# ignition_board_sch.net
KiCad netlist of a schematic drawn in EAGLE
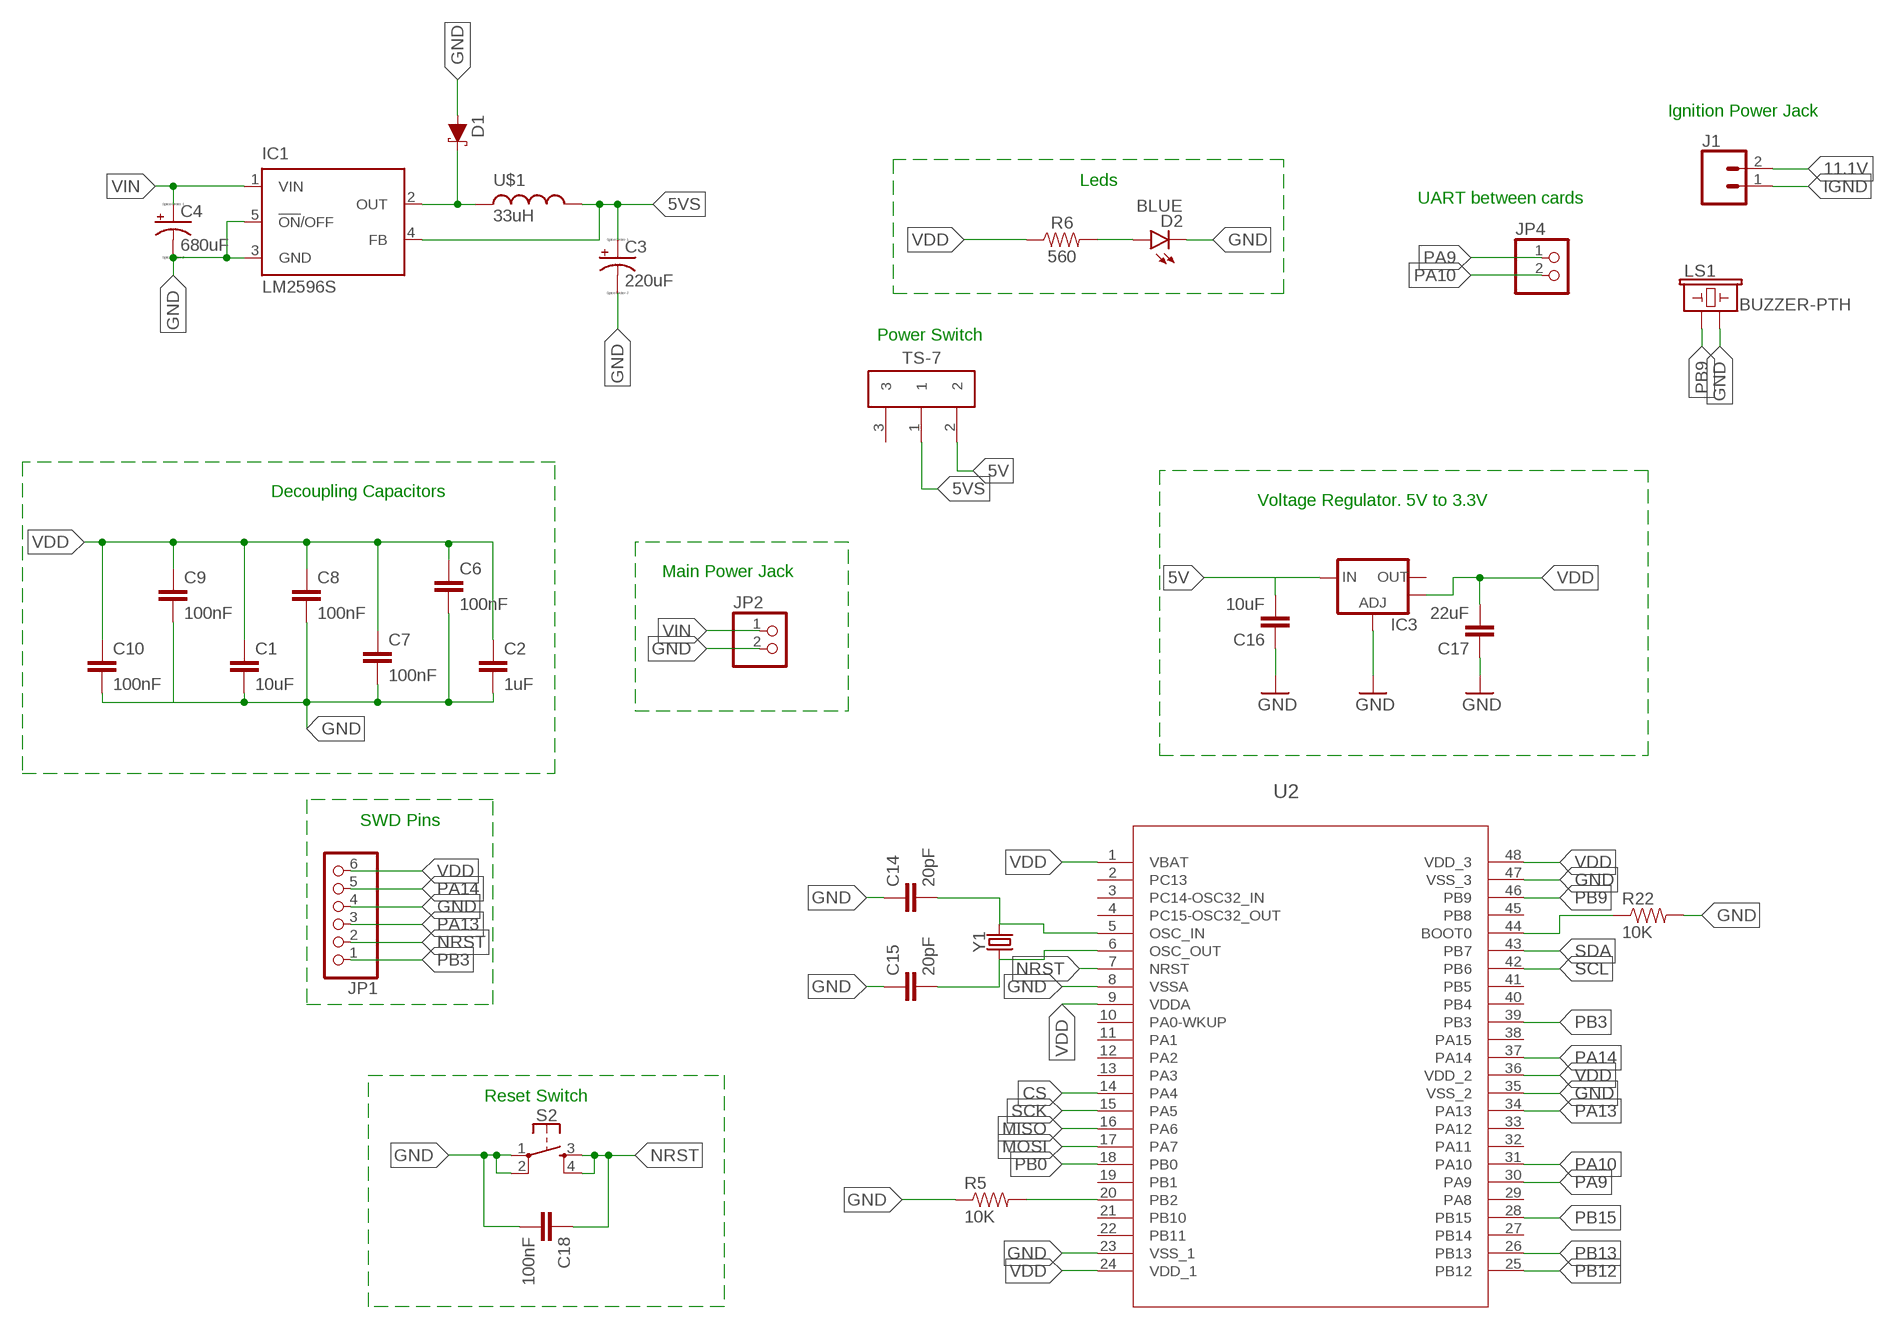
[diagram p0: schematic, sheet 1, part 1 of 2]
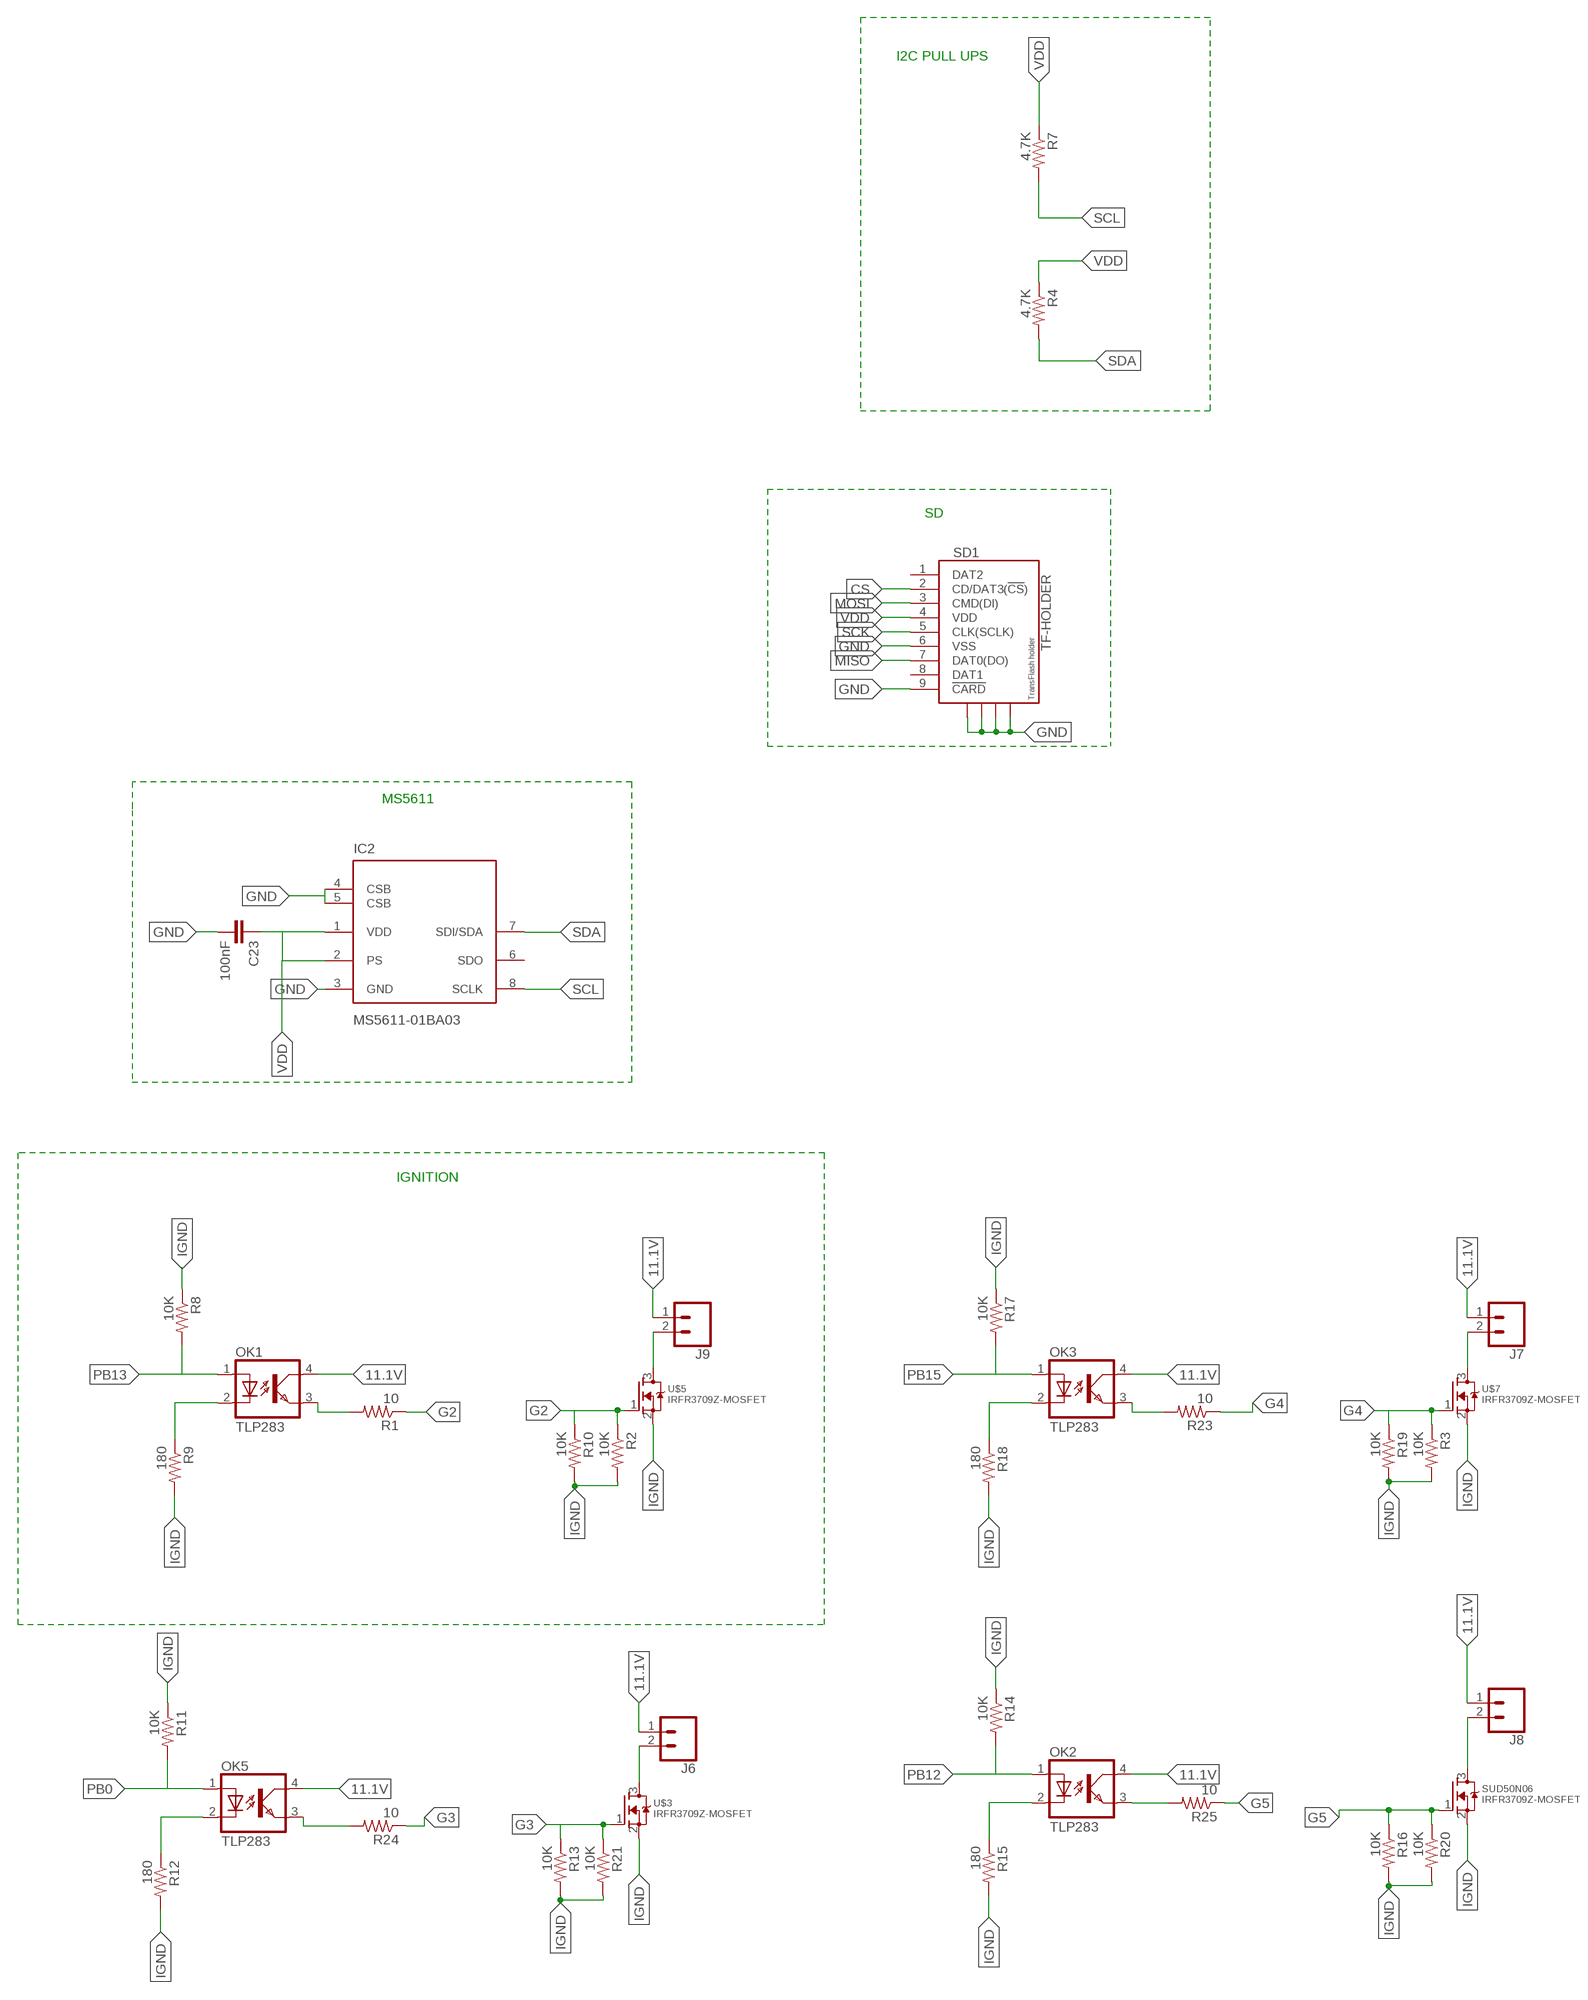
[diagram p1: schematic, sheet 1, part 2 of 2]

(export (version "E")
  (design (tool "Eeschema 10.0.6"))
  (components
    (comp (ref "C1")
      (value "10uF")
      (footprint "eagle-import:0805")
      (libsource (lib "eagle-import") (part "10UF-0805-10V-10%"))
    )
    (comp (ref "C2")
      (value "1uF")
      (footprint "eagle-import:0805")
      (libsource (lib "eagle-import") (part "10UF-0805-10V-10%"))
    )
    (comp (ref "C3")
      (value "220uF")
      (footprint "eagle-import:TT5D7")
      (libsource (lib "eagle-import") (part "CPOL-USTT5D7"))
    )
    (comp (ref "C4")
      (value "680uF")
      (footprint "eagle-import:TT5D7")
      (libsource (lib "eagle-import") (part "CPOL-USTT5D7"))
    )
    (comp (ref "C6")
      (value "100nF")
      (footprint "eagle-import:0805")
      (libsource (lib "eagle-import") (part "10UF-0805-10V-10%"))
    )
    (comp (ref "C7")
      (value "100nF")
      (footprint "eagle-import:0805")
      (libsource (lib "eagle-import") (part "10UF-0805-10V-10%"))
    )
    (comp (ref "C8")
      (value "100nF")
      (footprint "eagle-import:0805")
      (libsource (lib "eagle-import") (part "10UF-0805-10V-10%"))
    )
    (comp (ref "C9")
      (value "100nF")
      (footprint "eagle-import:0805")
      (libsource (lib "eagle-import") (part "10UF-0805-10V-10%"))
    )
    (comp (ref "C10")
      (value "100nF")
      (footprint "eagle-import:0805")
      (libsource (lib "eagle-import") (part "10UF-0805-10V-10%"))
    )
    (comp (ref "C14")
      (value "20pF")
      (footprint "eagle-import:0805")
      (libsource (lib "eagle-import") (part "10UF-0805-10V-10%"))
    )
    (comp (ref "C15")
      (value "20pF")
      (footprint "eagle-import:0805")
      (libsource (lib "eagle-import") (part "10UF-0805-10V-10%"))
    )
    (comp (ref "C16")
      (value "10uF")
      (footprint "eagle-import:0805@2")
      (libsource (lib "eagle-import") (part "CAP0805"))
    )
    (comp (ref "C17")
      (value "22uF")
      (footprint "eagle-import:0805@2")
      (libsource (lib "eagle-import") (part "CAP0805"))
    )
    (comp (ref "C18")
      (value "100nF")
      (footprint "eagle-import:0805")
      (libsource (lib "eagle-import") (part "10UF-0805-10V-10%"))
    )
    (comp (ref "C23")
      (value "100nF")
      (footprint "eagle-import:0805@2")
      (libsource (lib "eagle-import") (part "CAP0805"))
    )
    (comp (ref "D1")
      (value "3A/40V/500mV")
      (footprint "eagle-import:SMA-DIODE")
      (libsource (lib "eagle-import") (part "DIODE-SCHOTTKY-B340A"))
    )
    (comp (ref "D2")
      (value "BLUE")
      (footprint "eagle-import:LED-1206")
      (libsource (lib "eagle-import") (part "LED-BLUE1206"))
    )
    (comp (ref "IC1")
      (value "LM2596S")
      (footprint "eagle-import:TO263-5")
      (fields (field (name "MF") "NATIONAL SEMICONDUCTOR") (field (name "MPN") "LM2596S-ADJ/NOPB"))
      (libsource (lib "eagle-import") (part "LM2596S"))
    )
    (comp (ref "IC2")
      (value "MS5611-01BA03")
      (footprint "eagle-import:SON125P300X500X100-8N")
      (libsource (lib "eagle-import") (part "MS5611-01BA03"))
    )
    (comp (ref "IC3")
      (value "V_REG_LM1117SOT223")
      (footprint "eagle-import:SOT223")
      (libsource (lib "eagle-import") (part "V_REG_LM1117SOT223"))
    )
    (comp (ref "J1")
      (value "CONN_025MM")
      (footprint "eagle-import:SCREWTERMINAL-5MM-2")
      (libsource (lib "eagle-import") (part "CONN_025MM"))
    )
    (comp (ref "J6")
      (value "CONN_025MM")
      (footprint "eagle-import:SCREWTERMINAL-5MM-2")
      (libsource (lib "eagle-import") (part "CONN_025MM"))
    )
    (comp (ref "J7")
      (value "CONN_025MM")
      (footprint "eagle-import:SCREWTERMINAL-5MM-2")
      (libsource (lib "eagle-import") (part "CONN_025MM"))
    )
    (comp (ref "J8")
      (value "CONN_025MM")
      (footprint "eagle-import:SCREWTERMINAL-5MM-2")
      (libsource (lib "eagle-import") (part "CONN_025MM"))
    )
    (comp (ref "J9")
      (value "CONN_025MM")
      (footprint "eagle-import:SCREWTERMINAL-5MM-2")
      (libsource (lib "eagle-import") (part "CONN_025MM"))
    )
    (comp (ref "JP1")
      (value "PINHD-1X6")
      (footprint "eagle-import:1X06")
      (libsource (lib "eagle-import") (part "PINHD-1X6"))
    )
    (comp (ref "JP2")
      (value "PINHD-1X2")
      (footprint "eagle-import:1X02")
      (libsource (lib "eagle-import") (part "PINHD-1X2"))
    )
    (comp (ref "JP4")
      (value "PINHD-1X2/90")
      (footprint "eagle-import:1X02_90")
      (libsource (lib "eagle-import") (part "PINHD-1X2/90"))
    )
    (comp (ref "LS1")
      (value "BUZZER-PTH")
      (footprint "eagle-import:BUZZER-12MM")
      (libsource (lib "eagle-import") (part "BUZZER-PTH"))
    )
    (comp (ref "OK1")
      (value "TLP283")
      (footprint "eagle-import:MINI-FLAT-4")
      (libsource (lib "eagle-import") (part "TLP283"))
    )
    (comp (ref "OK2")
      (value "TLP283")
      (footprint "eagle-import:MINI-FLAT-4")
      (libsource (lib "eagle-import") (part "TLP283"))
    )
    (comp (ref "OK3")
      (value "TLP283")
      (footprint "eagle-import:MINI-FLAT-4")
      (libsource (lib "eagle-import") (part "TLP283"))
    )
    (comp (ref "OK5")
      (value "TLP283")
      (footprint "eagle-import:MINI-FLAT-4")
      (libsource (lib "eagle-import") (part "TLP283"))
    )
    (comp (ref "R1")
      (value "10")
      (footprint "eagle-import:0805")
      (libsource (lib "eagle-import") (part "RESISTOR0805-RES"))
    )
    (comp (ref "R2")
      (value "10K")
      (footprint "eagle-import:0805")
      (libsource (lib "eagle-import") (part "RESISTOR0805-RES"))
    )
    (comp (ref "R3")
      (value "10K")
      (footprint "eagle-import:0805")
      (libsource (lib "eagle-import") (part "RESISTOR0805-RES"))
    )
    (comp (ref "R4")
      (value "4.7K")
      (footprint "eagle-import:0805")
      (libsource (lib "eagle-import") (part "RESISTOR0805-RES"))
    )
    (comp (ref "R5")
      (value "10K")
      (footprint "eagle-import:0805")
      (libsource (lib "eagle-import") (part "RESISTOR0805-RES"))
    )
    (comp (ref "R6")
      (value "560")
      (footprint "eagle-import:0805@1")
      (libsource (lib "eagle-import") (part "0.3OHM-0805-1/8W-1%"))
    )
    (comp (ref "R7")
      (value "4.7K")
      (footprint "eagle-import:0805")
      (libsource (lib "eagle-import") (part "RESISTOR0805-RES"))
    )
    (comp (ref "R8")
      (value "10K")
      (footprint "eagle-import:0805")
      (libsource (lib "eagle-import") (part "RESISTOR0805-RES"))
    )
    (comp (ref "R9")
      (value "180")
      (footprint "eagle-import:0805")
      (libsource (lib "eagle-import") (part "RESISTOR0805-RES"))
    )
    (comp (ref "R10")
      (value "10K")
      (footprint "eagle-import:0805")
      (libsource (lib "eagle-import") (part "RESISTOR0805-RES"))
    )
    (comp (ref "R11")
      (value "10K")
      (footprint "eagle-import:0805")
      (libsource (lib "eagle-import") (part "RESISTOR0805-RES"))
    )
    (comp (ref "R12")
      (value "180")
      (footprint "eagle-import:0805")
      (libsource (lib "eagle-import") (part "RESISTOR0805-RES"))
    )
    (comp (ref "R13")
      (value "10K")
      (footprint "eagle-import:0805")
      (libsource (lib "eagle-import") (part "RESISTOR0805-RES"))
    )
    (comp (ref "R14")
      (value "10K")
      (footprint "eagle-import:0805")
      (libsource (lib "eagle-import") (part "RESISTOR0805-RES"))
    )
    (comp (ref "R15")
      (value "180")
      (footprint "eagle-import:0805")
      (libsource (lib "eagle-import") (part "RESISTOR0805-RES"))
    )
    (comp (ref "R16")
      (value "10K")
      (footprint "eagle-import:0805")
      (libsource (lib "eagle-import") (part "RESISTOR0805-RES"))
    )
    (comp (ref "R17")
      (value "10K")
      (footprint "eagle-import:0805")
      (libsource (lib "eagle-import") (part "RESISTOR0805-RES"))
    )
    (comp (ref "R18")
      (value "180")
      (footprint "eagle-import:0805")
      (libsource (lib "eagle-import") (part "RESISTOR0805-RES"))
    )
    (comp (ref "R19")
      (value "10K")
      (footprint "eagle-import:0805")
      (libsource (lib "eagle-import") (part "RESISTOR0805-RES"))
    )
    (comp (ref "R20")
      (value "10K")
      (footprint "eagle-import:0805")
      (libsource (lib "eagle-import") (part "RESISTOR0805-RES"))
    )
    (comp (ref "R21")
      (value "10K")
      (footprint "eagle-import:0805")
      (libsource (lib "eagle-import") (part "RESISTOR0805-RES"))
    )
    (comp (ref "R22")
      (value "10K")
      (footprint "eagle-import:0805")
      (libsource (lib "eagle-import") (part "RESISTOR0805-RES"))
    )
    (comp (ref "R23")
      (value "10")
      (footprint "eagle-import:0805")
      (libsource (lib "eagle-import") (part "RESISTOR0805-RES"))
    )
    (comp (ref "R24")
      (value "10")
      (footprint "eagle-import:0805")
      (libsource (lib "eagle-import") (part "RESISTOR0805-RES"))
    )
    (comp (ref "R25")
      (value "10")
      (footprint "eagle-import:0805")
      (libsource (lib "eagle-import") (part "RESISTOR0805-RES"))
    )
    (comp (ref "S2")
      (value "MOMENTARY-SWITCH-SPST-2-SMD-5.2MM")
      (footprint "eagle-import:TACTILE_SWITCH_SMD_5.2MM")
      (libsource (lib "eagle-import") (part "MOMENTARY-SWITCH-SPST-2-SMD-5.2MM"))
    )
    (comp (ref "SD1")
      (value "TF-HOLDER")
      (footprint "eagle-import:TF-PULL")
      (libsource (lib "eagle-import") (part "TF-HOLDER"))
    )
    (comp (ref "SUD50N06")
      (value "IRFR3709Z-MOSFET")
      (footprint "eagle-import:TO252")
      (libsource (lib "eagle-import") (part "IRFR3709Z-MOSFET"))
    )
    (comp (ref "TS-7")
      (value "TS-7")
      (footprint "eagle-import:TS7")
      (libsource (lib "eagle-import") (part "TS-7"))
    )
    (comp (ref "U$1")
      (value "33uH")
      (footprint "eagle-import:MSS1260")
      (libsource (lib "eagle-import") (part "MSS1260"))
    )
    (comp (ref "U$3")
      (value "IRFR3709Z-MOSFET")
      (footprint "eagle-import:TO252")
      (libsource (lib "eagle-import") (part "IRFR3709Z-MOSFET"))
    )
    (comp (ref "U$5")
      (value "IRFR3709Z-MOSFET")
      (footprint "eagle-import:TO252")
      (libsource (lib "eagle-import") (part "IRFR3709Z-MOSFET"))
    )
    (comp (ref "U$7")
      (value "IRFR3709Z-MOSFET")
      (footprint "eagle-import:TO252")
      (libsource (lib "eagle-import") (part "IRFR3709Z-MOSFET"))
    )
    (comp (ref "U2")
      (value "STM32F103CXT2")
      (footprint "eagle-import:LQFP48-7X7MM")
      (fields (field (name "MANUFACTURER_PART_NUMBER") "stm32f103cxt2"))
      (libsource (lib "eagle-import") (part "STM32F103CXT2"))
    )
    (comp (ref "Y1")
      (value "CRYSTALPTH-HC49US")
      (footprint "eagle-import:HC49US")
      (libsource (lib "eagle-import") (part "CRYSTALPTH-HC49US"))
    )
  )
  (nets
    (net (code "1") (name "5V") (class "Default")
      (node (ref "C16") (pin "2") (pinfunction "2_2") (pintype "passive"))
      (node (ref "IC3") (pin "3") (pinfunction "IN_3") (pintype "input"))
      (node (ref "TS-7") (pin "2") (pinfunction "2_2") (pintype "bidirectional"))
    )
    (net (code "2") (name "5VS") (class "Default")
      (node (ref "C3") (pin "+") (pinfunction "+_+") (pintype "passive"))
      (node (ref "IC1") (pin "4") (pinfunction "FB_4") (pintype "input"))
      (node (ref "TS-7") (pin "1") (pinfunction "1_1") (pintype "bidirectional"))
      (node (ref "U$1") (pin "P$1") (pinfunction "P$1_P$1") (pintype "passive"))
    )
    (net (code "3") (name "11.1V") (class "Default")
      (node (ref "J1") (pin "2") (pinfunction "2_2") (pintype "passive"))
      (node (ref "J6") (pin "1") (pinfunction "1_1") (pintype "passive"))
      (node (ref "J7") (pin "1") (pinfunction "1_1") (pintype "passive"))
      (node (ref "J8") (pin "1") (pinfunction "1_1") (pintype "passive"))
      (node (ref "J9") (pin "1") (pinfunction "1_1") (pintype "passive"))
      (node (ref "OK1") (pin "4") (pinfunction "COL_4") (pintype "passive"))
      (node (ref "OK2") (pin "4") (pinfunction "COL_4") (pintype "passive"))
      (node (ref "OK3") (pin "4") (pinfunction "COL_4") (pintype "passive"))
      (node (ref "OK5") (pin "4") (pinfunction "COL_4") (pintype "passive"))
    )
    (net (code "4") (name "CS") (class "Default")
      (node (ref "SD1") (pin "2") (pinfunction "CD/DAT3(~{CS})_2") (pintype "bidirectional"))
      (node (ref "U2") (pin "14") (pinfunction "PA4_14") (pintype "bidirectional"))
    )
    (net (code "5") (name "G2") (class "Default")
      (node (ref "R1") (pin "1") (pinfunction "1_1") (pintype "passive"))
      (node (ref "R10") (pin "1") (pinfunction "1_1") (pintype "passive"))
      (node (ref "R2") (pin "1") (pinfunction "1_1") (pintype "passive"))
      (node (ref "U$5") (pin "1") (pinfunction "G_1") (pintype "bidirectional"))
    )
    (net (code "6") (name "G3") (class "Default")
      (node (ref "R13") (pin "1") (pinfunction "1_1") (pintype "passive"))
      (node (ref "R21") (pin "1") (pinfunction "1_1") (pintype "passive"))
      (node (ref "R24") (pin "1") (pinfunction "1_1") (pintype "passive"))
      (node (ref "U$3") (pin "1") (pinfunction "G_1") (pintype "bidirectional"))
    )
    (net (code "7") (name "G4") (class "Default")
      (node (ref "R19") (pin "1") (pinfunction "1_1") (pintype "passive"))
      (node (ref "R23") (pin "1") (pinfunction "1_1") (pintype "passive"))
      (node (ref "R3") (pin "1") (pinfunction "1_1") (pintype "passive"))
      (node (ref "U$7") (pin "1") (pinfunction "G_1") (pintype "bidirectional"))
    )
    (net (code "8") (name "G5") (class "Default")
      (node (ref "R16") (pin "1") (pinfunction "1_1") (pintype "passive"))
      (node (ref "R20") (pin "1") (pinfunction "1_1") (pintype "passive"))
      (node (ref "R25") (pin "1") (pinfunction "1_1") (pintype "passive"))
      (node (ref "SUD50N06") (pin "1") (pinfunction "G_1") (pintype "bidirectional"))
    )
    (net (code "9") (name "GND") (class "Default")
      (node (ref "C1") (pin "2") (pinfunction "2_2") (pintype "passive"))
      (node (ref "C10") (pin "2") (pinfunction "2_2") (pintype "passive"))
      (node (ref "C14") (pin "1") (pinfunction "1_1") (pintype "passive"))
      (node (ref "C15") (pin "1") (pinfunction "1_1") (pintype "passive"))
      (node (ref "C16") (pin "1") (pinfunction "1_1") (pintype "passive"))
      (node (ref "C17") (pin "1") (pinfunction "1_1") (pintype "passive"))
      (node (ref "C18") (pin "2") (pinfunction "2_2") (pintype "passive"))
      (node (ref "C2") (pin "2") (pinfunction "2_2") (pintype "passive"))
      (node (ref "C23") (pin "2") (pinfunction "2_2") (pintype "passive"))
      (node (ref "C3") (pin "-") (pinfunction "-_-") (pintype "passive"))
      (node (ref "C4") (pin "-") (pinfunction "-_-") (pintype "passive"))
      (node (ref "C6") (pin "2") (pinfunction "2_2") (pintype "passive"))
      (node (ref "C7") (pin "2") (pinfunction "2_2") (pintype "passive"))
      (node (ref "C8") (pin "2") (pinfunction "2_2") (pintype "passive"))
      (node (ref "C9") (pin "2") (pinfunction "2_2") (pintype "passive"))
      (node (ref "D1") (pin "A") (pinfunction "A_A") (pintype "passive"))
      (node (ref "D2") (pin "C") (pinfunction "C_C") (pintype "passive"))
      (node (ref "IC1") (pin "3") (pinfunction "GND_3") (pintype "power_in"))
      (node (ref "IC1") (pin "5") (pinfunction "~{ON}/OFF_5") (pintype "input"))
      (node (ref "IC2") (pin "3") (pinfunction "GND_3") (pintype "power_in"))
      (node (ref "IC2") (pin "4") (pinfunction "CSB_4") (pintype "input"))
      (node (ref "IC2") (pin "5") (pinfunction "CSB_5") (pintype "input"))
      (node (ref "IC3") (pin "1") (pinfunction "ADJ_1") (pintype "input"))
      (node (ref "JP1") (pin "4") (pinfunction "4_4") (pintype "passive"))
      (node (ref "JP2") (pin "2") (pinfunction "2_2") (pintype "passive"))
      (node (ref "LS1") (pin "-") (pinfunction "2_-") (pintype "passive"))
      (node (ref "R22") (pin "2") (pinfunction "2_2") (pintype "passive"))
      (node (ref "R5") (pin "1") (pinfunction "1_1") (pintype "passive"))
      (node (ref "S2") (pin "1") (pinfunction "1_1") (pintype "passive"))
      (node (ref "S2") (pin "2") (pinfunction "2_2") (pintype "passive"))
      (node (ref "SD1") (pin "6") (pinfunction "VSS_6") (pintype "power_in"))
      (node (ref "SD1") (pin "9") (pinfunction "~{CARD}_9") (pintype "passive"))
      (node (ref "SD1") (pin "S1") (pinfunction "S1_S1") (pintype "passive"))
      (node (ref "SD1") (pin "S2") (pinfunction "S2_S2") (pintype "passive"))
      (node (ref "SD1") (pin "S3") (pinfunction "S3_S3") (pintype "passive"))
      (node (ref "SD1") (pin "S4") (pinfunction "S4_S4") (pintype "passive"))
      (node (ref "U2") (pin "23") (pinfunction "VSS_1_23") (pintype "power_in"))
      (node (ref "U2") (pin "35") (pinfunction "VSS_2_35") (pintype "power_in"))
      (node (ref "U2") (pin "47") (pinfunction "VSS_3_47") (pintype "power_in"))
      (node (ref "U2") (pin "8") (pinfunction "VSSA_8") (pintype "power_in"))
    )
    (net (code "10") (name "IGND") (class "Default")
      (node (ref "J1") (pin "1") (pinfunction "1_1") (pintype "passive"))
      (node (ref "R10") (pin "2") (pinfunction "2_2") (pintype "passive"))
      (node (ref "R11") (pin "1") (pinfunction "1_1") (pintype "passive"))
      (node (ref "R12") (pin "2") (pinfunction "2_2") (pintype "passive"))
      (node (ref "R13") (pin "2") (pinfunction "2_2") (pintype "passive"))
      (node (ref "R14") (pin "1") (pinfunction "1_1") (pintype "passive"))
      (node (ref "R15") (pin "2") (pinfunction "2_2") (pintype "passive"))
      (node (ref "R16") (pin "2") (pinfunction "2_2") (pintype "passive"))
      (node (ref "R17") (pin "1") (pinfunction "1_1") (pintype "passive"))
      (node (ref "R18") (pin "2") (pinfunction "2_2") (pintype "passive"))
      (node (ref "R19") (pin "2") (pinfunction "2_2") (pintype "passive"))
      (node (ref "R2") (pin "2") (pinfunction "2_2") (pintype "passive"))
      (node (ref "R20") (pin "2") (pinfunction "2_2") (pintype "passive"))
      (node (ref "R21") (pin "2") (pinfunction "2_2") (pintype "passive"))
      (node (ref "R3") (pin "2") (pinfunction "2_2") (pintype "passive"))
      (node (ref "R8") (pin "1") (pinfunction "1_1") (pintype "passive"))
      (node (ref "R9") (pin "2") (pinfunction "2_2") (pintype "passive"))
      (node (ref "SUD50N06") (pin "2") (pinfunction "S_2") (pintype "bidirectional"))
      (node (ref "U$3") (pin "2") (pinfunction "S_2") (pintype "bidirectional"))
      (node (ref "U$5") (pin "2") (pinfunction "S_2") (pintype "bidirectional"))
      (node (ref "U$7") (pin "2") (pinfunction "S_2") (pintype "bidirectional"))
    )
    (net (code "11") (name "MISO") (class "Default")
      (node (ref "SD1") (pin "7") (pinfunction "DAT0(DO)_7") (pintype "bidirectional"))
      (node (ref "U2") (pin "16") (pinfunction "PA6_16") (pintype "bidirectional"))
    )
    (net (code "12") (name "MOSI") (class "Default")
      (node (ref "SD1") (pin "3") (pinfunction "CMD(DI)_3") (pintype "bidirectional"))
      (node (ref "U2") (pin "17") (pinfunction "PA7_17") (pintype "bidirectional"))
    )
    (net (code "13") (name "NRST") (class "Default")
      (node (ref "C18") (pin "1") (pinfunction "1_1") (pintype "passive"))
      (node (ref "JP1") (pin "2") (pinfunction "2_2") (pintype "passive"))
      (node (ref "S2") (pin "3") (pinfunction "3_3") (pintype "passive"))
      (node (ref "S2") (pin "4") (pinfunction "4_4") (pintype "passive"))
      (node (ref "U2") (pin "7") (pinfunction "NRST_7") (pintype "bidirectional"))
    )
    (net (code "14") (name "Net-(D2-PadA)") (class "Default")
      (node (ref "D2") (pin "A") (pinfunction "A_A") (pintype "passive"))
      (node (ref "R6") (pin "2") (pinfunction "2_2") (pintype "passive"))
    )
    (net (code "15") (name "Net-(IC1-OUT)") (class "Default")
      (node (ref "D1") (pin "C") (pinfunction "C_C") (pintype "passive"))
      (node (ref "IC1") (pin "2") (pinfunction "OUT_2") (pintype "output"))
      (node (ref "U$1") (pin "P$2") (pinfunction "P$2_P$2") (pintype "passive"))
    )
    (net (code "16") (name "Net-(OK1-C)") (class "Default")
      (node (ref "OK1") (pin "2") (pinfunction "C_2") (pintype "passive"))
      (node (ref "R9") (pin "1") (pinfunction "1_1") (pintype "passive"))
    )
    (net (code "17") (name "Net-(OK1-EMIT)") (class "Default")
      (node (ref "OK1") (pin "3") (pinfunction "EMIT_3") (pintype "passive"))
      (node (ref "R1") (pin "2") (pinfunction "2_2") (pintype "passive"))
    )
    (net (code "18") (name "Net-(OK2-C)") (class "Default")
      (node (ref "OK2") (pin "2") (pinfunction "C_2") (pintype "passive"))
      (node (ref "R15") (pin "1") (pinfunction "1_1") (pintype "passive"))
    )
    (net (code "19") (name "Net-(OK2-EMIT)") (class "Default")
      (node (ref "OK2") (pin "3") (pinfunction "EMIT_3") (pintype "passive"))
      (node (ref "R25") (pin "2") (pinfunction "2_2") (pintype "passive"))
    )
    (net (code "20") (name "Net-(OK3-C)") (class "Default")
      (node (ref "OK3") (pin "2") (pinfunction "C_2") (pintype "passive"))
      (node (ref "R18") (pin "1") (pinfunction "1_1") (pintype "passive"))
    )
    (net (code "21") (name "Net-(OK3-EMIT)") (class "Default")
      (node (ref "OK3") (pin "3") (pinfunction "EMIT_3") (pintype "passive"))
      (node (ref "R23") (pin "2") (pinfunction "2_2") (pintype "passive"))
    )
    (net (code "22") (name "Net-(OK5-C)") (class "Default")
      (node (ref "OK5") (pin "2") (pinfunction "C_2") (pintype "passive"))
      (node (ref "R12") (pin "1") (pinfunction "1_1") (pintype "passive"))
    )
    (net (code "23") (name "Net-(OK5-EMIT)") (class "Default")
      (node (ref "OK5") (pin "3") (pinfunction "EMIT_3") (pintype "passive"))
      (node (ref "R24") (pin "2") (pinfunction "2_2") (pintype "passive"))
    )
    (net (code "24") (name "Net-(SUD50N06-D)") (class "Default")
      (node (ref "J8") (pin "2") (pinfunction "2_2") (pintype "passive"))
      (node (ref "SUD50N06") (pin "3") (pinfunction "D_3") (pintype "bidirectional"))
    )
    (net (code "25") (name "Net-(U$3-D)") (class "Default")
      (node (ref "J6") (pin "2") (pinfunction "2_2") (pintype "passive"))
      (node (ref "U$3") (pin "3") (pinfunction "D_3") (pintype "bidirectional"))
    )
    (net (code "26") (name "Net-(U$5-D)") (class "Default")
      (node (ref "J9") (pin "2") (pinfunction "2_2") (pintype "passive"))
      (node (ref "U$5") (pin "3") (pinfunction "D_3") (pintype "bidirectional"))
    )
    (net (code "27") (name "Net-(U$7-D)") (class "Default")
      (node (ref "J7") (pin "2") (pinfunction "2_2") (pintype "passive"))
      (node (ref "U$7") (pin "3") (pinfunction "D_3") (pintype "bidirectional"))
    )
    (net (code "28") (name "Net-(U2-BOOT0)") (class "Default")
      (node (ref "R22") (pin "1") (pinfunction "1_1") (pintype "passive"))
      (node (ref "U2") (pin "44") (pinfunction "BOOT0_44") (pintype "input"))
    )
    (net (code "29") (name "Net-(U2-OSC_IN)") (class "Default")
      (node (ref "C14") (pin "2") (pinfunction "2_2") (pintype "passive"))
      (node (ref "U2") (pin "5") (pinfunction "OSC_IN_5") (pintype "input"))
      (node (ref "Y1") (pin "2") (pinfunction "2_2") (pintype "passive"))
    )
    (net (code "30") (name "Net-(U2-OSC_OUT)") (class "Default")
      (node (ref "C15") (pin "2") (pinfunction "2_2") (pintype "passive"))
      (node (ref "U2") (pin "6") (pinfunction "OSC_OUT_6") (pintype "output"))
      (node (ref "Y1") (pin "1") (pinfunction "1_1") (pintype "passive"))
    )
    (net (code "31") (name "Net-(U2-PB2)") (class "Default")
      (node (ref "R5") (pin "2") (pinfunction "2_2") (pintype "passive"))
      (node (ref "U2") (pin "20") (pinfunction "PB2_20") (pintype "bidirectional"))
    )
    (net (code "32") (name "PA9") (class "Default")
      (node (ref "JP4") (pin "1") (pinfunction "1_1") (pintype "passive"))
      (node (ref "U2") (pin "30") (pinfunction "PA9_30") (pintype "bidirectional"))
    )
    (net (code "33") (name "PA10") (class "Default")
      (node (ref "JP4") (pin "2") (pinfunction "2_2") (pintype "passive"))
      (node (ref "U2") (pin "31") (pinfunction "PA10_31") (pintype "bidirectional"))
    )
    (net (code "34") (name "PA13") (class "Default")
      (node (ref "JP1") (pin "3") (pinfunction "3_3") (pintype "passive"))
      (node (ref "U2") (pin "34") (pinfunction "PA13_34") (pintype "bidirectional"))
    )
    (net (code "35") (name "PA14") (class "Default")
      (node (ref "JP1") (pin "5") (pinfunction "5_5") (pintype "passive"))
      (node (ref "U2") (pin "37") (pinfunction "PA14_37") (pintype "bidirectional"))
    )
    (net (code "36") (name "PB0") (class "Default")
      (node (ref "OK5") (pin "1") (pinfunction "A_1") (pintype "passive"))
      (node (ref "R11") (pin "2") (pinfunction "2_2") (pintype "passive"))
      (node (ref "U2") (pin "18") (pinfunction "PB0_18") (pintype "bidirectional"))
    )
    (net (code "37") (name "PB3") (class "Default")
      (node (ref "JP1") (pin "1") (pinfunction "1_1") (pintype "passive"))
      (node (ref "U2") (pin "39") (pinfunction "PB3_39") (pintype "bidirectional"))
    )
    (net (code "38") (name "PB9") (class "Default")
      (node (ref "LS1") (pin "+") (pinfunction "1_+") (pintype "passive"))
      (node (ref "U2") (pin "46") (pinfunction "PB9_46") (pintype "bidirectional"))
    )
    (net (code "39") (name "PB12") (class "Default")
      (node (ref "OK2") (pin "1") (pinfunction "A_1") (pintype "passive"))
      (node (ref "R14") (pin "2") (pinfunction "2_2") (pintype "passive"))
      (node (ref "U2") (pin "25") (pinfunction "PB12_25") (pintype "bidirectional"))
    )
    (net (code "40") (name "PB13") (class "Default")
      (node (ref "OK1") (pin "1") (pinfunction "A_1") (pintype "passive"))
      (node (ref "R8") (pin "2") (pinfunction "2_2") (pintype "passive"))
      (node (ref "U2") (pin "26") (pinfunction "PB13_26") (pintype "bidirectional"))
    )
    (net (code "41") (name "PB15") (class "Default")
      (node (ref "OK3") (pin "1") (pinfunction "A_1") (pintype "passive"))
      (node (ref "R17") (pin "2") (pinfunction "2_2") (pintype "passive"))
      (node (ref "U2") (pin "28") (pinfunction "PB15_28") (pintype "bidirectional"))
    )
    (net (code "42") (name "SCK") (class "Default")
      (node (ref "SD1") (pin "5") (pinfunction "CLK(SCLK)_5") (pintype "input"))
      (node (ref "U2") (pin "15") (pinfunction "PA5_15") (pintype "bidirectional"))
    )
    (net (code "43") (name "SCL") (class "Default")
      (node (ref "IC2") (pin "8") (pinfunction "SCLK_8") (pintype "input"))
      (node (ref "R7") (pin "2") (pinfunction "2_2") (pintype "passive"))
      (node (ref "U2") (pin "42") (pinfunction "PB6_42") (pintype "bidirectional"))
    )
    (net (code "44") (name "SDA") (class "Default")
      (node (ref "IC2") (pin "7") (pinfunction "SDI/SDA_7") (pintype "bidirectional"))
      (node (ref "R4") (pin "2") (pinfunction "2_2") (pintype "passive"))
      (node (ref "U2") (pin "43") (pinfunction "PB7_43") (pintype "bidirectional"))
    )
    (net (code "45") (name "VDD") (class "Default")
      (node (ref "C1") (pin "1") (pinfunction "1_1") (pintype "passive"))
      (node (ref "C10") (pin "1") (pinfunction "1_1") (pintype "passive"))
      (node (ref "C17") (pin "2") (pinfunction "2_2") (pintype "passive"))
      (node (ref "C2") (pin "1") (pinfunction "1_1") (pintype "passive"))
      (node (ref "C23") (pin "1") (pinfunction "1_1") (pintype "passive"))
      (node (ref "C6") (pin "1") (pinfunction "1_1") (pintype "passive"))
      (node (ref "C7") (pin "1") (pinfunction "1_1") (pintype "passive"))
      (node (ref "C8") (pin "1") (pinfunction "1_1") (pintype "passive"))
      (node (ref "C9") (pin "1") (pinfunction "1_1") (pintype "passive"))
      (node (ref "IC2") (pin "1") (pinfunction "VDD_1") (pintype "power_in"))
      (node (ref "IC2") (pin "2") (pinfunction "PS_2") (pintype "input"))
      (node (ref "IC3") (pin "4") (pinfunction "OUT_4") (pintype "output"))
      (node (ref "JP1") (pin "6") (pinfunction "6_6") (pintype "passive"))
      (node (ref "R4") (pin "1") (pinfunction "1_1") (pintype "passive"))
      (node (ref "R6") (pin "1") (pinfunction "1_1") (pintype "passive"))
      (node (ref "R7") (pin "1") (pinfunction "1_1") (pintype "passive"))
      (node (ref "SD1") (pin "4") (pinfunction "VDD_4") (pintype "power_in"))
      (node (ref "U2") (pin "1") (pinfunction "VBAT_1") (pintype "power_in"))
      (node (ref "U2") (pin "24") (pinfunction "VDD_1_24") (pintype "power_in"))
      (node (ref "U2") (pin "36") (pinfunction "VDD_2_36") (pintype "power_in"))
      (node (ref "U2") (pin "48") (pinfunction "VDD_3_48") (pintype "power_in"))
      (node (ref "U2") (pin "9") (pinfunction "VDDA_9") (pintype "power_in"))
    )
    (net (code "46") (name "VIN") (class "Default")
      (node (ref "C4") (pin "+") (pinfunction "+_+") (pintype "passive"))
      (node (ref "IC1") (pin "1") (pinfunction "VIN_1") (pintype "input"))
      (node (ref "JP2") (pin "1") (pinfunction "1_1") (pintype "passive"))
    )
    (net (code "47") (name "unconnected-(IC2-SDO-Pad6)") (class "Default")
      (node (ref "IC2") (pin "6") (pinfunction "SDO_6") (pintype "output"))
    )
    (net (code "48") (name "unconnected-(IC3-OUT-Pad2)") (class "Default")
      (node (ref "IC3") (pin "2") (pinfunction "OUT_2") (pintype "output"))
    )
    (net (code "49") (name "unconnected-(SD1-DAT1-Pad8)") (class "Default")
      (node (ref "SD1") (pin "8") (pinfunction "DAT1_8") (pintype "bidirectional"))
    )
    (net (code "50") (name "unconnected-(SD1-DAT2-Pad1)") (class "Default")
      (node (ref "SD1") (pin "1") (pinfunction "DAT2_1") (pintype "bidirectional"))
    )
    (net (code "51") (name "unconnected-(TS-7-Pad3)") (class "Default")
      (node (ref "TS-7") (pin "3") (pinfunction "3_3") (pintype "bidirectional"))
    )
    (net (code "52") (name "unconnected-(U2-PA0-WKUP-Pad10)") (class "Default")
      (node (ref "U2") (pin "10") (pinfunction "PA0-WKUP_10") (pintype "bidirectional"))
    )
    (net (code "53") (name "unconnected-(U2-PA1-Pad11)") (class "Default")
      (node (ref "U2") (pin "11") (pinfunction "PA1_11") (pintype "bidirectional"))
    )
    (net (code "54") (name "unconnected-(U2-PA2-Pad12)") (class "Default")
      (node (ref "U2") (pin "12") (pinfunction "PA2_12") (pintype "bidirectional"))
    )
    (net (code "55") (name "unconnected-(U2-PA3-Pad13)") (class "Default")
      (node (ref "U2") (pin "13") (pinfunction "PA3_13") (pintype "bidirectional"))
    )
    (net (code "56") (name "unconnected-(U2-PA8-Pad29)") (class "Default")
      (node (ref "U2") (pin "29") (pinfunction "PA8_29") (pintype "bidirectional"))
    )
    (net (code "57") (name "unconnected-(U2-PA11-Pad32)") (class "Default")
      (node (ref "U2") (pin "32") (pinfunction "PA11_32") (pintype "bidirectional"))
    )
    (net (code "58") (name "unconnected-(U2-PA12-Pad33)") (class "Default")
      (node (ref "U2") (pin "33") (pinfunction "PA12_33") (pintype "bidirectional"))
    )
    (net (code "59") (name "unconnected-(U2-PA15-Pad38)") (class "Default")
      (node (ref "U2") (pin "38") (pinfunction "PA15_38") (pintype "bidirectional"))
    )
    (net (code "60") (name "unconnected-(U2-PB1-Pad19)") (class "Default")
      (node (ref "U2") (pin "19") (pinfunction "PB1_19") (pintype "bidirectional"))
    )
    (net (code "61") (name "unconnected-(U2-PB4-Pad40)") (class "Default")
      (node (ref "U2") (pin "40") (pinfunction "PB4_40") (pintype "bidirectional"))
    )
    (net (code "62") (name "unconnected-(U2-PB5-Pad41)") (class "Default")
      (node (ref "U2") (pin "41") (pinfunction "PB5_41") (pintype "bidirectional"))
    )
    (net (code "63") (name "unconnected-(U2-PB8-Pad45)") (class "Default")
      (node (ref "U2") (pin "45") (pinfunction "PB8_45") (pintype "bidirectional"))
    )
    (net (code "64") (name "unconnected-(U2-PB10-Pad21)") (class "Default")
      (node (ref "U2") (pin "21") (pinfunction "PB10_21") (pintype "bidirectional"))
    )
    (net (code "65") (name "unconnected-(U2-PB11-Pad22)") (class "Default")
      (node (ref "U2") (pin "22") (pinfunction "PB11_22") (pintype "bidirectional"))
    )
    (net (code "66") (name "unconnected-(U2-PB14-Pad27)") (class "Default")
      (node (ref "U2") (pin "27") (pinfunction "PB14_27") (pintype "bidirectional"))
    )
    (net (code "67") (name "unconnected-(U2-PC13-Pad2)") (class "Default")
      (node (ref "U2") (pin "2") (pinfunction "PC13_2") (pintype "bidirectional"))
    )
    (net (code "68") (name "unconnected-(U2-PC14-OSC32_IN-Pad3)") (class "Default")
      (node (ref "U2") (pin "3") (pinfunction "PC14-OSC32_IN_3") (pintype "bidirectional"))
    )
    (net (code "69") (name "unconnected-(U2-PC15-OSC32_OUT-Pad4)") (class "Default")
      (node (ref "U2") (pin "4") (pinfunction "PC15-OSC32_OUT_4") (pintype "bidirectional"))
    )
  )
)
